# Lab_10_-_Schematic.net
KiCad netlist of a schematic drawn in EAGLE
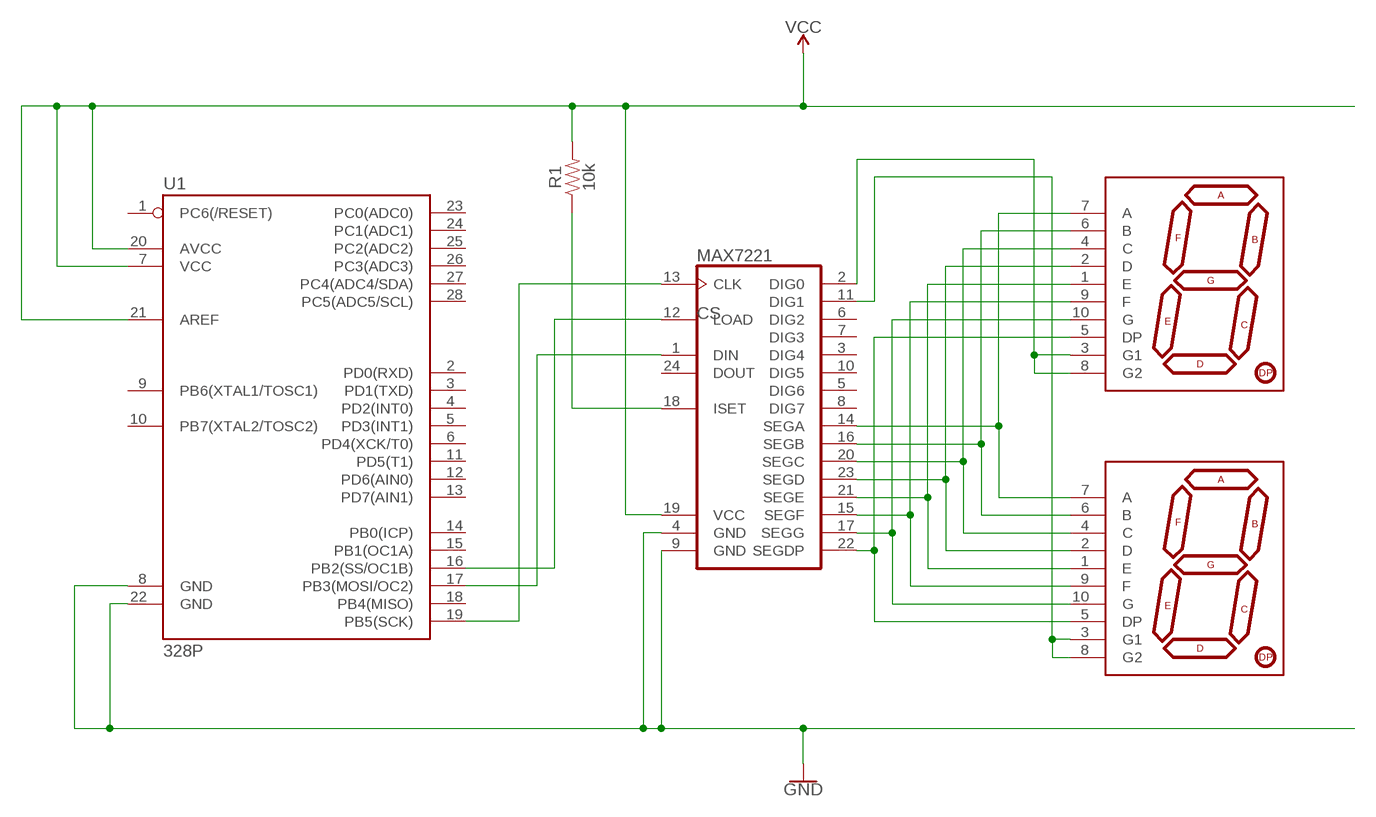
[diagram p0: schematic, sheet 1]

(export (version "E")
  (design (tool "Eeschema 10.0.6"))
  (components
    (comp (ref "MAX7221")
      (value "MAX7219CNG")
      (footprint "eagle-import:DIL24-3")
      (fields (field (name "MF") "MAXIM"))
      (libsource (lib "eagle-import") (part "MAX7219CNG"))
    )
    (comp (ref "R1")
      (value "10k")
      (footprint "eagle-import:AXIAL-0.3")
      (libsource (lib "eagle-import") (part "10KOHM-HORIZ-1/4W-1%"))
    )
    (comp (ref "U$1")
      (value "YSD-160AB3C-8")
      (footprint "eagle-import:7-SEGMENT-1_PTH")
      (libsource (lib "eagle-import") (part "7-SEGMENT-1DIGIT-1INCH-BLUE"))
    )
    (comp (ref "U$2")
      (value "YSD-160AB3C-8")
      (footprint "eagle-import:7-SEGMENT-1_PTH")
      (libsource (lib "eagle-import") (part "7-SEGMENT-1DIGIT-1INCH-BLUE"))
    )
    (comp (ref "U1")
      (value "328P")
      (footprint "eagle-import:DIP28")
      (libsource (lib "eagle-import") (part "ATMEGA328P_PDIP"))
    )
  )
  (nets
    (net (code "1") (name "/CS") (class "Default")
      (node (ref "MAX7221") (pin "12") (pinfunction "LOAD_12") (pintype "input"))
      (node (ref "U1") (pin "16") (pinfunction "PB2(SS/OC1B)_16") (pintype "bidirectional"))
    )
    (net (code "2") (name "GND") (class "Default")
      (node (ref "MAX7221") (pin "4") (pinfunction "GND_4") (pintype "power_in"))
      (node (ref "MAX7221") (pin "9") (pinfunction "GND_9") (pintype "power_in"))
      (node (ref "U1") (pin "22") (pinfunction "GND_22") (pintype "bidirectional"))
      (node (ref "U1") (pin "8") (pinfunction "GND_8") (pintype "bidirectional"))
    )
    (net (code "3") (name "Net-(MAX7221-CLK)") (class "Default")
      (node (ref "MAX7221") (pin "13") (pinfunction "CLK_13") (pintype "input"))
      (node (ref "U1") (pin "19") (pinfunction "PB5(SCK)_19") (pintype "bidirectional"))
    )
    (net (code "4") (name "Net-(MAX7221-DIG0)") (class "Default")
      (node (ref "MAX7221") (pin "2") (pinfunction "DIG0_2") (pintype "output"))
      (node (ref "U$1") (pin "3") (pinfunction "G1_3") (pintype "bidirectional"))
      (node (ref "U$1") (pin "8") (pinfunction "G2_8") (pintype "bidirectional"))
    )
    (net (code "5") (name "Net-(MAX7221-DIG1)") (class "Default")
      (node (ref "MAX7221") (pin "11") (pinfunction "DIG1_11") (pintype "output"))
      (node (ref "U$2") (pin "3") (pinfunction "G1_3") (pintype "bidirectional"))
      (node (ref "U$2") (pin "8") (pinfunction "G2_8") (pintype "bidirectional"))
    )
    (net (code "6") (name "Net-(MAX7221-DIN)") (class "Default")
      (node (ref "MAX7221") (pin "1") (pinfunction "DIN_1") (pintype "input"))
      (node (ref "U1") (pin "17") (pinfunction "PB3(MOSI/OC2)_17") (pintype "bidirectional"))
    )
    (net (code "7") (name "Net-(MAX7221-ISET)") (class "Default")
      (node (ref "MAX7221") (pin "18") (pinfunction "ISET_18") (pintype "input"))
      (node (ref "R1") (pin "P$1") (pinfunction "1_P$1") (pintype "passive"))
    )
    (net (code "8") (name "Net-(MAX7221-SEGA)") (class "Default")
      (node (ref "MAX7221") (pin "14") (pinfunction "SEGA_14") (pintype "output"))
      (node (ref "U$1") (pin "7") (pinfunction "A_7") (pintype "bidirectional"))
      (node (ref "U$2") (pin "7") (pinfunction "A_7") (pintype "bidirectional"))
    )
    (net (code "9") (name "Net-(MAX7221-SEGB)") (class "Default")
      (node (ref "MAX7221") (pin "16") (pinfunction "SEGB_16") (pintype "output"))
      (node (ref "U$1") (pin "6") (pinfunction "B_6") (pintype "bidirectional"))
      (node (ref "U$2") (pin "6") (pinfunction "B_6") (pintype "bidirectional"))
    )
    (net (code "10") (name "Net-(MAX7221-SEGC)") (class "Default")
      (node (ref "MAX7221") (pin "20") (pinfunction "SEGC_20") (pintype "output"))
      (node (ref "U$1") (pin "4") (pinfunction "C_4") (pintype "bidirectional"))
      (node (ref "U$2") (pin "4") (pinfunction "C_4") (pintype "bidirectional"))
    )
    (net (code "11") (name "Net-(MAX7221-SEGD)") (class "Default")
      (node (ref "MAX7221") (pin "23") (pinfunction "SEGD_23") (pintype "output"))
      (node (ref "U$1") (pin "2") (pinfunction "D_2") (pintype "bidirectional"))
      (node (ref "U$2") (pin "2") (pinfunction "D_2") (pintype "bidirectional"))
    )
    (net (code "12") (name "Net-(MAX7221-SEGDP)") (class "Default")
      (node (ref "MAX7221") (pin "22") (pinfunction "SEGDP_22") (pintype "output"))
      (node (ref "U$1") (pin "5") (pinfunction "DP_5") (pintype "bidirectional"))
      (node (ref "U$2") (pin "5") (pinfunction "DP_5") (pintype "bidirectional"))
    )
    (net (code "13") (name "Net-(MAX7221-SEGE)") (class "Default")
      (node (ref "MAX7221") (pin "21") (pinfunction "SEGE_21") (pintype "output"))
      (node (ref "U$1") (pin "1") (pinfunction "E_1") (pintype "bidirectional"))
      (node (ref "U$2") (pin "1") (pinfunction "E_1") (pintype "bidirectional"))
    )
    (net (code "14") (name "Net-(MAX7221-SEGF)") (class "Default")
      (node (ref "MAX7221") (pin "15") (pinfunction "SEGF_15") (pintype "output"))
      (node (ref "U$1") (pin "9") (pinfunction "F_9") (pintype "bidirectional"))
      (node (ref "U$2") (pin "9") (pinfunction "F_9") (pintype "bidirectional"))
    )
    (net (code "15") (name "Net-(MAX7221-SEGG)") (class "Default")
      (node (ref "MAX7221") (pin "17") (pinfunction "SEGG_17") (pintype "output"))
      (node (ref "U$1") (pin "10") (pinfunction "G_10") (pintype "bidirectional"))
      (node (ref "U$2") (pin "10") (pinfunction "G_10") (pintype "bidirectional"))
    )
    (net (code "16") (name "VCC") (class "Default")
      (node (ref "MAX7221") (pin "19") (pinfunction "VCC_19") (pintype "power_in"))
      (node (ref "R1") (pin "P$2") (pinfunction "2_P$2") (pintype "passive"))
      (node (ref "U1") (pin "20") (pinfunction "AVCC_20") (pintype "bidirectional"))
      (node (ref "U1") (pin "21") (pinfunction "AREF_21") (pintype "bidirectional"))
      (node (ref "U1") (pin "7") (pinfunction "VCC_7") (pintype "bidirectional"))
    )
    (net (code "17") (name "unconnected-(MAX7221-DIG2-Pad6)") (class "Default")
      (node (ref "MAX7221") (pin "6") (pinfunction "DIG2_6") (pintype "output"))
    )
    (net (code "18") (name "unconnected-(MAX7221-DIG3-Pad7)") (class "Default")
      (node (ref "MAX7221") (pin "7") (pinfunction "DIG3_7") (pintype "output"))
    )
    (net (code "19") (name "unconnected-(MAX7221-DIG4-Pad3)") (class "Default")
      (node (ref "MAX7221") (pin "3") (pinfunction "DIG4_3") (pintype "output"))
    )
    (net (code "20") (name "unconnected-(MAX7221-DIG5-Pad10)") (class "Default")
      (node (ref "MAX7221") (pin "10") (pinfunction "DIG5_10") (pintype "output"))
    )
    (net (code "21") (name "unconnected-(MAX7221-DIG6-Pad5)") (class "Default")
      (node (ref "MAX7221") (pin "5") (pinfunction "DIG6_5") (pintype "output"))
    )
    (net (code "22") (name "unconnected-(MAX7221-DIG7-Pad8)") (class "Default")
      (node (ref "MAX7221") (pin "8") (pinfunction "DIG7_8") (pintype "output"))
    )
    (net (code "23") (name "unconnected-(MAX7221-DOUT-Pad24)") (class "Default")
      (node (ref "MAX7221") (pin "24") (pinfunction "DOUT_24") (pintype "output"))
    )
    (net (code "24") (name "unconnected-(U1-PB0(ICP)-Pad14)") (class "Default")
      (node (ref "U1") (pin "14") (pinfunction "PB0(ICP)_14") (pintype "bidirectional"))
    )
    (net (code "25") (name "unconnected-(U1-PB1(OC1A)-Pad15)") (class "Default")
      (node (ref "U1") (pin "15") (pinfunction "PB1(OC1A)_15") (pintype "bidirectional"))
    )
    (net (code "26") (name "unconnected-(U1-PB4(MISO)-Pad18)") (class "Default")
      (node (ref "U1") (pin "18") (pinfunction "PB4(MISO)_18") (pintype "bidirectional"))
    )
    (net (code "27") (name "unconnected-(U1-PB6(XTAL1{slash}TOSC1)-Pad9)") (class "Default")
      (node (ref "U1") (pin "9") (pinfunction "PB6(XTAL1/TOSC1)_9") (pintype "bidirectional"))
    )
    (net (code "28") (name "unconnected-(U1-PB7(XTAL2{slash}TOSC2)-Pad10)") (class "Default")
      (node (ref "U1") (pin "10") (pinfunction "PB7(XTAL2/TOSC2)_10") (pintype "bidirectional"))
    )
    (net (code "29") (name "unconnected-(U1-PC0(ADC0)-Pad23)") (class "Default")
      (node (ref "U1") (pin "23") (pinfunction "PC0(ADC0)_23") (pintype "bidirectional"))
    )
    (net (code "30") (name "unconnected-(U1-PC1(ADC1)-Pad24)") (class "Default")
      (node (ref "U1") (pin "24") (pinfunction "PC1(ADC1)_24") (pintype "bidirectional"))
    )
    (net (code "31") (name "unconnected-(U1-PC2(ADC2)-Pad25)") (class "Default")
      (node (ref "U1") (pin "25") (pinfunction "PC2(ADC2)_25") (pintype "bidirectional"))
    )
    (net (code "32") (name "unconnected-(U1-PC3(ADC3)-Pad26)") (class "Default")
      (node (ref "U1") (pin "26") (pinfunction "PC3(ADC3)_26") (pintype "bidirectional"))
    )
    (net (code "33") (name "unconnected-(U1-PC4(ADC4{slash}SDA)-Pad27)") (class "Default")
      (node (ref "U1") (pin "27") (pinfunction "PC4(ADC4/SDA)_27") (pintype "bidirectional"))
    )
    (net (code "34") (name "unconnected-(U1-PC5(ADC5{slash}SCL)-Pad28)") (class "Default")
      (node (ref "U1") (pin "28") (pinfunction "PC5(ADC5/SCL)_28") (pintype "bidirectional"))
    )
    (net (code "35") (name "unconnected-(U1-PC6({slash}RESET)-Pad1)") (class "Default")
      (node (ref "U1") (pin "1") (pinfunction "PC6(/RESET)_1") (pintype "bidirectional"))
    )
    (net (code "36") (name "unconnected-(U1-PD0(RXD)-Pad2)") (class "Default")
      (node (ref "U1") (pin "2") (pinfunction "PD0(RXD)_2") (pintype "bidirectional"))
    )
    (net (code "37") (name "unconnected-(U1-PD1(TXD)-Pad3)") (class "Default")
      (node (ref "U1") (pin "3") (pinfunction "PD1(TXD)_3") (pintype "bidirectional"))
    )
    (net (code "38") (name "unconnected-(U1-PD2(INT0)-Pad4)") (class "Default")
      (node (ref "U1") (pin "4") (pinfunction "PD2(INT0)_4") (pintype "bidirectional"))
    )
    (net (code "39") (name "unconnected-(U1-PD3(INT1)-Pad5)") (class "Default")
      (node (ref "U1") (pin "5") (pinfunction "PD3(INT1)_5") (pintype "bidirectional"))
    )
    (net (code "40") (name "unconnected-(U1-PD4(XCK{slash}T0)-Pad6)") (class "Default")
      (node (ref "U1") (pin "6") (pinfunction "PD4(XCK/T0)_6") (pintype "bidirectional"))
    )
    (net (code "41") (name "unconnected-(U1-PD5(T1)-Pad11)") (class "Default")
      (node (ref "U1") (pin "11") (pinfunction "PD5(T1)_11") (pintype "bidirectional"))
    )
    (net (code "42") (name "unconnected-(U1-PD6(AIN0)-Pad12)") (class "Default")
      (node (ref "U1") (pin "12") (pinfunction "PD6(AIN0)_12") (pintype "bidirectional"))
    )
    (net (code "43") (name "unconnected-(U1-PD7(AIN1)-Pad13)") (class "Default")
      (node (ref "U1") (pin "13") (pinfunction "PD7(AIN1)_13") (pintype "bidirectional"))
    )
  )
)
